# arduino_isp_v2.net
KiCad netlist of a schematic drawn in EAGLE
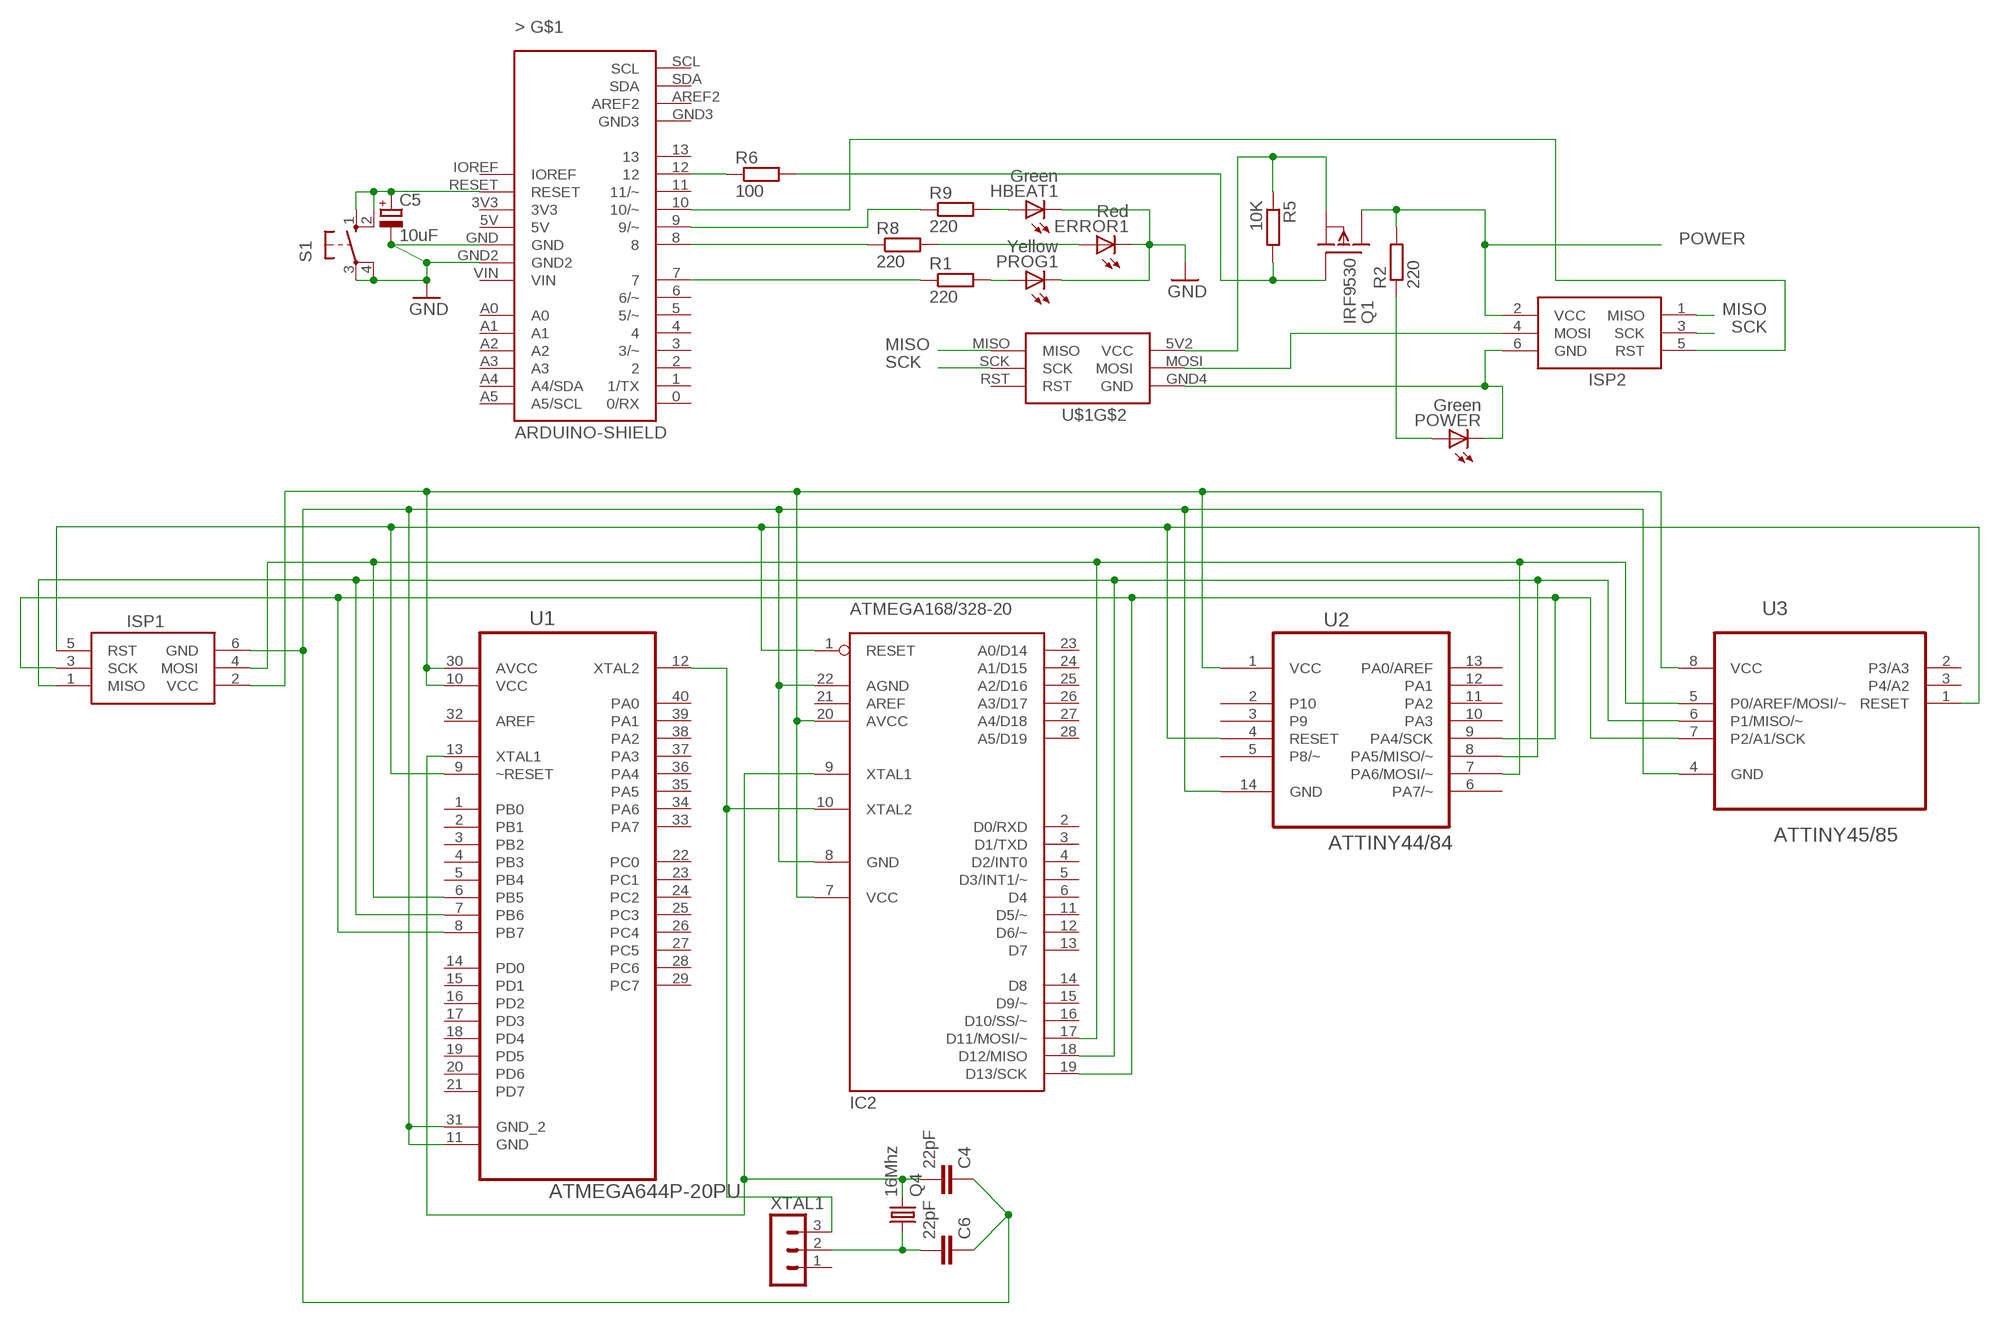
[diagram p0: schematic, sheet 1]

(export (version "E")
  (design (tool "Eeschema 10.0.6"))
  (components
    (comp (ref "C4")
      (value "22pF")
      (footprint "eagle-import:C050-030X075")
      (libsource (lib "eagle-import") (part "C-EU050-030X075"))
    )
    (comp (ref "C5")
      (value "10uF")
      (footprint "eagle-import:E2,5-6E")
      (libsource (lib "eagle-import") (part "CPOL-EUE2,5-6E"))
    )
    (comp (ref "C6")
      (value "22pF")
      (footprint "eagle-import:C050-030X075")
      (libsource (lib "eagle-import") (part "C-EU050-030X075"))
    )
    (comp (ref "ERROR1")
      (value "Red")
      (footprint "eagle-import:LED5MM")
      (libsource (lib "eagle-import") (part "LED5MM"))
    )
    (comp (ref "HBEAT1")
      (value "Green")
      (footprint "eagle-import:LED5MM")
      (libsource (lib "eagle-import") (part "LED5MM"))
    )
    (comp (ref "IC2")
      (value "ATMEGA168/328-20")
      (footprint "eagle-import:DIL28-3")
      (libsource (lib "eagle-import") (part "ATMEGA168/328-20"))
    )
    (comp (ref "ISP1")
      (value "AVRISP-6")
      (footprint "eagle-import:AVRISP")
      (libsource (lib "eagle-import") (part "AVRISP-6"))
    )
    (comp (ref "ISP2")
      (value "AVRISP-6")
      (footprint "eagle-import:AVRISP")
      (libsource (lib "eagle-import") (part "AVRISP-6"))
    )
    (comp (ref "POWER")
      (value "Green")
      (footprint "eagle-import:LED5MM")
      (libsource (lib "eagle-import") (part "LED5MM"))
    )
    (comp (ref "PROG1")
      (value "Yellow")
      (footprint "eagle-import:LED5MM")
      (libsource (lib "eagle-import") (part "LED5MM"))
    )
    (comp (ref "Q1")
      (value "IRF9530")
      (footprint "eagle-import:TO220")
      (libsource (lib "eagle-import") (part "IRF9530"))
    )
    (comp (ref "Q4")
      (value "16Mhz")
      (footprint "eagle-import:HC49_S")
      (fields (field (name "OC_FARNELL") "1667008"))
      (libsource (lib "eagle-import") (part "CRYSTALHC49S"))
    )
    (comp (ref "R1")
      (value "220")
      (footprint "eagle-import:0207_10")
      (libsource (lib "eagle-import") (part "R-EU_0207/10"))
    )
    (comp (ref "R2")
      (value "220")
      (footprint "eagle-import:0207_10")
      (libsource (lib "eagle-import") (part "R-EU_0207/10"))
    )
    (comp (ref "R5")
      (value "10K")
      (footprint "eagle-import:0207_10")
      (libsource (lib "eagle-import") (part "R-EU_0207/10"))
    )
    (comp (ref "R6")
      (value "100")
      (footprint "eagle-import:0207_10")
      (libsource (lib "eagle-import") (part "R-EU_0207/10"))
    )
    (comp (ref "R8")
      (value "220")
      (footprint "eagle-import:0207_10")
      (libsource (lib "eagle-import") (part "R-EU_0207/10"))
    )
    (comp (ref "R9")
      (value "220")
      (footprint "eagle-import:0207_10")
      (libsource (lib "eagle-import") (part "R-EU_0207/10"))
    )
    (comp (ref "S1")
      (value "10-XX")
      (footprint "eagle-import:B3F-10XX")
      (fields (field (name "MPN") "B3F-1000"))
      (libsource (lib "eagle-import") (part "10-XX"))
    )
    (comp (ref "U$1")
      (value "ARDUINO-SHIELD")
      (footprint "eagle-import:ARDUINO-UNO-SHIELD")
      (libsource (lib "eagle-import") (part "ARDUINO-SHIELD"))
    )
    (comp (ref "U1")
      (value "ATMEGA644P-20PU")
      (footprint "eagle-import:DIP254P1524X482-40")
      (libsource (lib "eagle-import") (part "ATMEGA644P-20PU"))
    )
    (comp (ref "U2")
      (value "ATTINY44/84")
      (footprint "eagle-import:DIP254P762X533-14")
      (fields (field (name "MPN") "ATTINY44-20PU"))
      (libsource (lib "eagle-import") (part "ATTINY44/84"))
    )
    (comp (ref "U3")
      (value "ATTINY45/85")
      (footprint "eagle-import:DIP254P762X533-8")
      (fields (field (name "MPN") "ATTINY45-20PU"))
      (libsource (lib "eagle-import") (part "ATTINY45/85"))
    )
    (comp (ref "XTAL1")
      (value "MA03-1")
      (footprint "eagle-import:MA03-1")
      (fields (field (name "OC_FARNELL") "unknown") (field (name "OC_NEWARK") "unknown"))
      (libsource (lib "eagle-import") (part "MA03-1"))
    )
  )
  (nets
    (net (code "1") (name "/MISO") (class "Default")
      (node (ref "ISP2") (pin "1") (pinfunction "MISO_1") (pintype "input"))
      (node (ref "U$1") (pin "MISO") (pinfunction "MISO_MISO") (pintype "input"))
    )
    (net (code "2") (name "/POWER") (class "Default")
      (node (ref "ISP2") (pin "2") (pinfunction "VCC_2") (pintype "power_in"))
      (node (ref "Q1") (pin "2") (pinfunction "D_2") (pintype "passive"))
      (node (ref "R2") (pin "2") (pinfunction "2_2") (pintype "passive"))
    )
    (net (code "3") (name "/SCK") (class "Default")
      (node (ref "ISP2") (pin "3") (pinfunction "SCK_3") (pintype "output"))
      (node (ref "U$1") (pin "SCK") (pinfunction "SCK_SCK") (pintype "output"))
    )
    (net (code "4") (name "GND") (class "Default")
      (node (ref "C5") (pin "-") (pinfunction "-_-") (pintype "passive"))
      (node (ref "ERROR1") (pin "K") (pinfunction "C_K") (pintype "passive"))
      (node (ref "HBEAT1") (pin "K") (pinfunction "C_K") (pintype "passive"))
      (node (ref "PROG1") (pin "K") (pinfunction "C_K") (pintype "passive"))
      (node (ref "S1") (pin "3") (pinfunction "P_3") (pintype "passive"))
      (node (ref "S1") (pin "4") (pinfunction "P1_4") (pintype "passive"))
      (node (ref "U$1") (pin "GND") (pinfunction "GND_GND") (pintype "bidirectional"))
      (node (ref "U$1") (pin "GND2") (pinfunction "GND2_GND2") (pintype "bidirectional"))
    )
    (net (code "5") (name "Net-(C6-Pad2)") (class "Default")
      (node (ref "C6") (pin "2") (pinfunction "2_2") (pintype "passive"))
      (node (ref "Q4") (pin "1") (pinfunction "1_1") (pintype "passive"))
      (node (ref "XTAL1") (pin "2") (pinfunction "2_2") (pintype "passive"))
    )
    (net (code "6") (name "Net-(ERROR1-PadA)") (class "Default")
      (node (ref "ERROR1") (pin "A") (pinfunction "A_A") (pintype "passive"))
      (node (ref "R8") (pin "2") (pinfunction "2_2") (pintype "passive"))
    )
    (net (code "7") (name "Net-(HBEAT1-PadA)") (class "Default")
      (node (ref "HBEAT1") (pin "A") (pinfunction "A_A") (pintype "passive"))
      (node (ref "R9") (pin "2") (pinfunction "2_2") (pintype "passive"))
    )
    (net (code "8") (name "Net-(IC2-AGND)") (class "Default")
      (node (ref "C4") (pin "1") (pinfunction "1_1") (pintype "passive"))
      (node (ref "C6") (pin "1") (pinfunction "1_1") (pintype "passive"))
      (node (ref "IC2") (pin "22") (pinfunction "AGND_22") (pintype "bidirectional"))
      (node (ref "IC2") (pin "8") (pinfunction "GND_8") (pintype "bidirectional"))
      (node (ref "ISP1") (pin "6") (pinfunction "GND_6") (pintype "power_in"))
      (node (ref "U1") (pin "11") (pinfunction "GND_11") (pintype "passive"))
      (node (ref "U1") (pin "31") (pinfunction "GND_2_31") (pintype "passive"))
      (node (ref "U2") (pin "14") (pinfunction "GND_14") (pintype "passive"))
      (node (ref "U3") (pin "4") (pinfunction "GND_4") (pintype "passive"))
    )
    (net (code "9") (name "Net-(IC2-AVCC)") (class "Default")
      (node (ref "IC2") (pin "20") (pinfunction "AVCC_20") (pintype "bidirectional"))
      (node (ref "IC2") (pin "7") (pinfunction "VCC_7") (pintype "bidirectional"))
      (node (ref "ISP1") (pin "2") (pinfunction "VCC_2") (pintype "power_in"))
      (node (ref "U1") (pin "10") (pinfunction "VCC_10") (pintype "power_in"))
      (node (ref "U1") (pin "30") (pinfunction "AVCC_30") (pintype "power_in"))
      (node (ref "U2") (pin "1") (pinfunction "VCC_1") (pintype "power_in"))
      (node (ref "U3") (pin "8") (pinfunction "VCC_8") (pintype "power_in"))
    )
    (net (code "10") (name "Net-(IC2-D11{slash}MOSI{slash}~{})") (class "Default")
      (node (ref "IC2") (pin "17") (pinfunction "D11/MOSI/~{}_17") (pintype "bidirectional"))
      (node (ref "ISP1") (pin "4") (pinfunction "MOSI_4") (pintype "output"))
      (node (ref "U1") (pin "6") (pinfunction "PB5_6") (pintype "bidirectional"))
      (node (ref "U2") (pin "7") (pinfunction "PA6/MOSI/~{}_7") (pintype "bidirectional"))
      (node (ref "U3") (pin "5") (pinfunction "P0/AREF/MOSI/~{}_5") (pintype "bidirectional"))
    )
    (net (code "11") (name "Net-(IC2-D12{slash}MISO)") (class "Default")
      (node (ref "IC2") (pin "18") (pinfunction "D12/MISO_18") (pintype "bidirectional"))
      (node (ref "ISP1") (pin "1") (pinfunction "MISO_1") (pintype "input"))
      (node (ref "U1") (pin "7") (pinfunction "PB6_7") (pintype "bidirectional"))
      (node (ref "U2") (pin "8") (pinfunction "PA5/MISO/~{}_8") (pintype "bidirectional"))
      (node (ref "U3") (pin "6") (pinfunction "P1/MISO/~{}_6") (pintype "bidirectional"))
    )
    (net (code "12") (name "Net-(IC2-D13{slash}SCK)") (class "Default")
      (node (ref "IC2") (pin "19") (pinfunction "D13/SCK_19") (pintype "bidirectional"))
      (node (ref "ISP1") (pin "3") (pinfunction "SCK_3") (pintype "output"))
      (node (ref "U1") (pin "8") (pinfunction "PB7_8") (pintype "bidirectional"))
      (node (ref "U2") (pin "9") (pinfunction "PA4/SCK_9") (pintype "bidirectional"))
      (node (ref "U3") (pin "7") (pinfunction "P2/A1/SCK_7") (pintype "bidirectional"))
    )
    (net (code "13") (name "Net-(IC2-RESET)") (class "Default")
      (node (ref "IC2") (pin "1") (pinfunction "RESET_1") (pintype "bidirectional"))
      (node (ref "ISP1") (pin "5") (pinfunction "RST_5") (pintype "output"))
      (node (ref "U1") (pin "9") (pinfunction "~{RESET}_9") (pintype "input"))
      (node (ref "U2") (pin "4") (pinfunction "RESET_4") (pintype "bidirectional"))
      (node (ref "U3") (pin "1") (pinfunction "RESET_1") (pintype "bidirectional"))
    )
    (net (code "14") (name "Net-(IC2-XTAL1)") (class "Default")
      (node (ref "C4") (pin "2") (pinfunction "2_2") (pintype "passive"))
      (node (ref "IC2") (pin "9") (pinfunction "XTAL1_9") (pintype "bidirectional"))
      (node (ref "Q4") (pin "2") (pinfunction "2_2") (pintype "passive"))
      (node (ref "U1") (pin "13") (pinfunction "XTAL1_13") (pintype "input"))
    )
    (net (code "15") (name "Net-(IC2-XTAL2)") (class "Default")
      (node (ref "IC2") (pin "10") (pinfunction "XTAL2_10") (pintype "bidirectional"))
      (node (ref "U1") (pin "12") (pinfunction "XTAL2_12") (pintype "output"))
      (node (ref "XTAL1") (pin "3") (pinfunction "3_3") (pintype "passive"))
    )
    (net (code "16") (name "Net-(ISP2-GND)") (class "Default")
      (node (ref "ISP2") (pin "6") (pinfunction "GND_6") (pintype "power_in"))
      (node (ref "POWER") (pin "K") (pinfunction "C_K") (pintype "passive"))
      (node (ref "U$1") (pin "GND4") (pinfunction "GND_GND4") (pintype "power_in"))
    )
    (net (code "17") (name "Net-(ISP2-MOSI)") (class "Default")
      (node (ref "ISP2") (pin "4") (pinfunction "MOSI_4") (pintype "output"))
      (node (ref "U$1") (pin "MOSI") (pinfunction "MOSI_MOSI") (pintype "output"))
    )
    (net (code "18") (name "Net-(ISP2-RST)") (class "Default")
      (node (ref "ISP2") (pin "5") (pinfunction "RST_5") (pintype "output"))
      (node (ref "U$1") (pin "10") (pinfunction "10/~{}_10") (pintype "bidirectional"))
    )
    (net (code "19") (name "Net-(POWER-PadA)") (class "Default")
      (node (ref "POWER") (pin "A") (pinfunction "A_A") (pintype "passive"))
      (node (ref "R2") (pin "1") (pinfunction "1_1") (pintype "passive"))
    )
    (net (code "20") (name "Net-(PROG1-PadA)") (class "Default")
      (node (ref "PROG1") (pin "A") (pinfunction "A_A") (pintype "passive"))
      (node (ref "R1") (pin "2") (pinfunction "2_2") (pintype "passive"))
    )
    (net (code "21") (name "Net-(Q1-G)") (class "Default")
      (node (ref "Q1") (pin "1") (pinfunction "G_1") (pintype "passive"))
      (node (ref "R5") (pin "2") (pinfunction "2_2") (pintype "passive"))
      (node (ref "R6") (pin "2") (pinfunction "2_2") (pintype "passive"))
    )
    (net (code "22") (name "Net-(Q1-S)") (class "Default")
      (node (ref "Q1") (pin "3") (pinfunction "S_3") (pintype "passive"))
      (node (ref "R5") (pin "1") (pinfunction "1_1") (pintype "passive"))
      (node (ref "U$1") (pin "5V2") (pinfunction "VCC_5V2") (pintype "power_in"))
    )
    (net (code "23") (name "Net-(R1-Pad1)") (class "Default")
      (node (ref "R1") (pin "1") (pinfunction "1_1") (pintype "passive"))
      (node (ref "U$1") (pin "7") (pinfunction "7_7") (pintype "bidirectional"))
    )
    (net (code "24") (name "Net-(R6-Pad1)") (class "Default")
      (node (ref "R6") (pin "1") (pinfunction "1_1") (pintype "passive"))
      (node (ref "U$1") (pin "12") (pinfunction "12_12") (pintype "bidirectional"))
    )
    (net (code "25") (name "Net-(R8-Pad1)") (class "Default")
      (node (ref "R8") (pin "1") (pinfunction "1_1") (pintype "passive"))
      (node (ref "U$1") (pin "8") (pinfunction "8_8") (pintype "bidirectional"))
    )
    (net (code "26") (name "Net-(S1-S)") (class "Default")
      (node (ref "C5") (pin "+") (pinfunction "+_+") (pintype "passive"))
      (node (ref "S1") (pin "1") (pinfunction "S_1") (pintype "passive"))
      (node (ref "S1") (pin "2") (pinfunction "S1_2") (pintype "passive"))
      (node (ref "U$1") (pin "RESET") (pinfunction "RESET_RESET") (pintype "bidirectional"))
    )
    (net (code "27") (name "Net-(U$1A-9{slash}~{})") (class "Default")
      (node (ref "R9") (pin "1") (pinfunction "1_1") (pintype "passive"))
      (node (ref "U$1") (pin "9") (pinfunction "9/~{}_9") (pintype "bidirectional"))
    )
    (net (code "28") (name "unconnected-(IC2-A0{slash}D14-Pad23)") (class "Default")
      (node (ref "IC2") (pin "23") (pinfunction "A0/D14_23") (pintype "bidirectional"))
    )
    (net (code "29") (name "unconnected-(IC2-A1{slash}D15-Pad24)") (class "Default")
      (node (ref "IC2") (pin "24") (pinfunction "A1/D15_24") (pintype "bidirectional"))
    )
    (net (code "30") (name "unconnected-(IC2-A2{slash}D16-Pad25)") (class "Default")
      (node (ref "IC2") (pin "25") (pinfunction "A2/D16_25") (pintype "bidirectional"))
    )
    (net (code "31") (name "unconnected-(IC2-A3{slash}D17-Pad26)") (class "Default")
      (node (ref "IC2") (pin "26") (pinfunction "A3/D17_26") (pintype "bidirectional"))
    )
    (net (code "32") (name "unconnected-(IC2-A4{slash}D18-Pad27)") (class "Default")
      (node (ref "IC2") (pin "27") (pinfunction "A4/D18_27") (pintype "bidirectional"))
    )
    (net (code "33") (name "unconnected-(IC2-A5{slash}D19-Pad28)") (class "Default")
      (node (ref "IC2") (pin "28") (pinfunction "A5/D19_28") (pintype "bidirectional"))
    )
    (net (code "34") (name "unconnected-(IC2-AREF-Pad21)") (class "Default")
      (node (ref "IC2") (pin "21") (pinfunction "AREF_21") (pintype "bidirectional"))
    )
    (net (code "35") (name "unconnected-(IC2-D0{slash}RXD-Pad2)") (class "Default")
      (node (ref "IC2") (pin "2") (pinfunction "D0/RXD_2") (pintype "bidirectional"))
    )
    (net (code "36") (name "unconnected-(IC2-D1{slash}TXD-Pad3)") (class "Default")
      (node (ref "IC2") (pin "3") (pinfunction "D1/TXD_3") (pintype "bidirectional"))
    )
    (net (code "37") (name "unconnected-(IC2-D2{slash}INT0-Pad4)") (class "Default")
      (node (ref "IC2") (pin "4") (pinfunction "D2/INT0_4") (pintype "bidirectional"))
    )
    (net (code "38") (name "unconnected-(IC2-D3{slash}INT1{slash}~{}-Pad5)") (class "Default")
      (node (ref "IC2") (pin "5") (pinfunction "D3/INT1/~{}_5") (pintype "bidirectional"))
    )
    (net (code "39") (name "unconnected-(IC2-D4-Pad6)") (class "Default")
      (node (ref "IC2") (pin "6") (pinfunction "D4_6") (pintype "bidirectional"))
    )
    (net (code "40") (name "unconnected-(IC2-D5{slash}~{}-Pad11)") (class "Default")
      (node (ref "IC2") (pin "11") (pinfunction "D5/~{}_11") (pintype "bidirectional"))
    )
    (net (code "41") (name "unconnected-(IC2-D6{slash}~{}-Pad12)") (class "Default")
      (node (ref "IC2") (pin "12") (pinfunction "D6/~{}_12") (pintype "bidirectional"))
    )
    (net (code "42") (name "unconnected-(IC2-D7-Pad13)") (class "Default")
      (node (ref "IC2") (pin "13") (pinfunction "D7_13") (pintype "bidirectional"))
    )
    (net (code "43") (name "unconnected-(IC2-D8-Pad14)") (class "Default")
      (node (ref "IC2") (pin "14") (pinfunction "D8_14") (pintype "bidirectional"))
    )
    (net (code "44") (name "unconnected-(IC2-D9{slash}~{}-Pad15)") (class "Default")
      (node (ref "IC2") (pin "15") (pinfunction "D9/~{}_15") (pintype "bidirectional"))
    )
    (net (code "45") (name "unconnected-(IC2-D10{slash}SS{slash}~{}-Pad16)") (class "Default")
      (node (ref "IC2") (pin "16") (pinfunction "D10/SS/~{}_16") (pintype "bidirectional"))
    )
    (net (code "46") (name "unconnected-(U$1-Pad2)") (class "Default")
      (node (ref "U$1") (pin "2") (pinfunction "2_2") (pintype "bidirectional"))
    )
    (net (code "47") (name "unconnected-(U$1-Pad3V3)") (class "Default")
      (node (ref "U$1") (pin "3V3") (pinfunction "3V3_3V3") (pintype "bidirectional"))
    )
    (net (code "48") (name "unconnected-(U$1-Pad4)") (class "Default")
      (node (ref "U$1") (pin "4") (pinfunction "4_4") (pintype "bidirectional"))
    )
    (net (code "49") (name "unconnected-(U$1-Pad5V)") (class "Default")
      (node (ref "U$1") (pin "5V") (pinfunction "5V_5V") (pintype "bidirectional"))
    )
    (net (code "50") (name "unconnected-(U$1-Pad13)") (class "Default")
      (node (ref "U$1") (pin "13") (pinfunction "13_13") (pintype "bidirectional"))
    )
    (net (code "51") (name "unconnected-(U$1-PadA0)") (class "Default")
      (node (ref "U$1") (pin "A0") (pinfunction "A0_A0") (pintype "bidirectional"))
    )
    (net (code "52") (name "unconnected-(U$1-PadA1)") (class "Default")
      (node (ref "U$1") (pin "A1") (pinfunction "A1_A1") (pintype "bidirectional"))
    )
    (net (code "53") (name "unconnected-(U$1-PadA2)") (class "Default")
      (node (ref "U$1") (pin "A2") (pinfunction "A2_A2") (pintype "bidirectional"))
    )
    (net (code "54") (name "unconnected-(U$1-PadA3)") (class "Default")
      (node (ref "U$1") (pin "A3") (pinfunction "A3_A3") (pintype "bidirectional"))
    )
    (net (code "55") (name "unconnected-(U$1-PadAREF2)") (class "Default")
      (node (ref "U$1") (pin "AREF2") (pinfunction "AREF2_AREF2") (pintype "bidirectional"))
    )
    (net (code "56") (name "unconnected-(U$1-PadGND3)") (class "Default")
      (node (ref "U$1") (pin "GND3") (pinfunction "GND3_GND3") (pintype "bidirectional"))
    )
    (net (code "57") (name "unconnected-(U$1-PadIOREF)") (class "Default")
      (node (ref "U$1") (pin "IOREF") (pinfunction "IOREF_IOREF") (pintype "bidirectional"))
    )
    (net (code "58") (name "unconnected-(U$1-PadRST)") (class "Default")
      (node (ref "U$1") (pin "RST") (pinfunction "RST_RST") (pintype "output"))
    )
    (net (code "59") (name "unconnected-(U$1-PadSCL)") (class "Default")
      (node (ref "U$1") (pin "SCL") (pinfunction "SCL_SCL") (pintype "bidirectional"))
    )
    (net (code "60") (name "unconnected-(U$1-PadSDA)") (class "Default")
      (node (ref "U$1") (pin "SDA") (pinfunction "SDA_SDA") (pintype "bidirectional"))
    )
    (net (code "61") (name "unconnected-(U$1-PadVIN)") (class "Default")
      (node (ref "U$1") (pin "VIN") (pinfunction "VIN_VIN") (pintype "bidirectional"))
    )
    (net (code "62") (name "unconnected-(U$1A-0{slash}RX-Pad0)") (class "Default")
      (node (ref "U$1") (pin "0") (pinfunction "0/RX_0") (pintype "bidirectional"))
    )
    (net (code "63") (name "unconnected-(U$1A-1{slash}TX-Pad1)") (class "Default")
      (node (ref "U$1") (pin "1") (pinfunction "1/TX_1") (pintype "bidirectional"))
    )
    (net (code "64") (name "unconnected-(U$1A-3{slash}~{}-Pad3)") (class "Default")
      (node (ref "U$1") (pin "3") (pinfunction "3/~{}_3") (pintype "bidirectional"))
    )
    (net (code "65") (name "unconnected-(U$1A-5{slash}~{}-Pad5)") (class "Default")
      (node (ref "U$1") (pin "5") (pinfunction "5/~{}_5") (pintype "bidirectional"))
    )
    (net (code "66") (name "unconnected-(U$1A-6{slash}~{}-Pad6)") (class "Default")
      (node (ref "U$1") (pin "6") (pinfunction "6/~{}_6") (pintype "bidirectional"))
    )
    (net (code "67") (name "unconnected-(U$1A-11{slash}~{}-Pad11)") (class "Default")
      (node (ref "U$1") (pin "11") (pinfunction "11/~{}_11") (pintype "bidirectional"))
    )
    (net (code "68") (name "unconnected-(U$1A-A4{slash}SDA-PadA4)") (class "Default")
      (node (ref "U$1") (pin "A4") (pinfunction "A4/SDA_A4") (pintype "bidirectional"))
    )
    (net (code "69") (name "unconnected-(U$1A-A5{slash}SCL-PadA5)") (class "Default")
      (node (ref "U$1") (pin "A5") (pinfunction "A5/SCL_A5") (pintype "bidirectional"))
    )
    (net (code "70") (name "unconnected-(U1-AREF-Pad32)") (class "Default")
      (node (ref "U1") (pin "32") (pinfunction "AREF_32") (pintype "input"))
    )
    (net (code "71") (name "unconnected-(U1-PA0-Pad40)") (class "Default")
      (node (ref "U1") (pin "40") (pinfunction "PA0_40") (pintype "bidirectional"))
    )
    (net (code "72") (name "unconnected-(U1-PA1-Pad39)") (class "Default")
      (node (ref "U1") (pin "39") (pinfunction "PA1_39") (pintype "bidirectional"))
    )
    (net (code "73") (name "unconnected-(U1-PA2-Pad38)") (class "Default")
      (node (ref "U1") (pin "38") (pinfunction "PA2_38") (pintype "bidirectional"))
    )
    (net (code "74") (name "unconnected-(U1-PA3-Pad37)") (class "Default")
      (node (ref "U1") (pin "37") (pinfunction "PA3_37") (pintype "bidirectional"))
    )
    (net (code "75") (name "unconnected-(U1-PA4-Pad36)") (class "Default")
      (node (ref "U1") (pin "36") (pinfunction "PA4_36") (pintype "bidirectional"))
    )
    (net (code "76") (name "unconnected-(U1-PA5-Pad35)") (class "Default")
      (node (ref "U1") (pin "35") (pinfunction "PA5_35") (pintype "bidirectional"))
    )
    (net (code "77") (name "unconnected-(U1-PA6-Pad34)") (class "Default")
      (node (ref "U1") (pin "34") (pinfunction "PA6_34") (pintype "bidirectional"))
    )
    (net (code "78") (name "unconnected-(U1-PA7-Pad33)") (class "Default")
      (node (ref "U1") (pin "33") (pinfunction "PA7_33") (pintype "bidirectional"))
    )
    (net (code "79") (name "unconnected-(U1-PB0-Pad1)") (class "Default")
      (node (ref "U1") (pin "1") (pinfunction "PB0_1") (pintype "bidirectional"))
    )
    (net (code "80") (name "unconnected-(U1-PB1-Pad2)") (class "Default")
      (node (ref "U1") (pin "2") (pinfunction "PB1_2") (pintype "bidirectional"))
    )
    (net (code "81") (name "unconnected-(U1-PB2-Pad3)") (class "Default")
      (node (ref "U1") (pin "3") (pinfunction "PB2_3") (pintype "bidirectional"))
    )
    (net (code "82") (name "unconnected-(U1-PB3-Pad4)") (class "Default")
      (node (ref "U1") (pin "4") (pinfunction "PB3_4") (pintype "bidirectional"))
    )
    (net (code "83") (name "unconnected-(U1-PB4-Pad5)") (class "Default")
      (node (ref "U1") (pin "5") (pinfunction "PB4_5") (pintype "bidirectional"))
    )
    (net (code "84") (name "unconnected-(U1-PC0-Pad22)") (class "Default")
      (node (ref "U1") (pin "22") (pinfunction "PC0_22") (pintype "bidirectional"))
    )
    (net (code "85") (name "unconnected-(U1-PC1-Pad23)") (class "Default")
      (node (ref "U1") (pin "23") (pinfunction "PC1_23") (pintype "bidirectional"))
    )
    (net (code "86") (name "unconnected-(U1-PC2-Pad24)") (class "Default")
      (node (ref "U1") (pin "24") (pinfunction "PC2_24") (pintype "bidirectional"))
    )
    (net (code "87") (name "unconnected-(U1-PC3-Pad25)") (class "Default")
      (node (ref "U1") (pin "25") (pinfunction "PC3_25") (pintype "bidirectional"))
    )
    (net (code "88") (name "unconnected-(U1-PC4-Pad26)") (class "Default")
      (node (ref "U1") (pin "26") (pinfunction "PC4_26") (pintype "bidirectional"))
    )
    (net (code "89") (name "unconnected-(U1-PC5-Pad27)") (class "Default")
      (node (ref "U1") (pin "27") (pinfunction "PC5_27") (pintype "bidirectional"))
    )
    (net (code "90") (name "unconnected-(U1-PC6-Pad28)") (class "Default")
      (node (ref "U1") (pin "28") (pinfunction "PC6_28") (pintype "bidirectional"))
    )
    (net (code "91") (name "unconnected-(U1-PC7-Pad29)") (class "Default")
      (node (ref "U1") (pin "29") (pinfunction "PC7_29") (pintype "bidirectional"))
    )
    (net (code "92") (name "unconnected-(U1-PD0-Pad14)") (class "Default")
      (node (ref "U1") (pin "14") (pinfunction "PD0_14") (pintype "bidirectional"))
    )
    (net (code "93") (name "unconnected-(U1-PD1-Pad15)") (class "Default")
      (node (ref "U1") (pin "15") (pinfunction "PD1_15") (pintype "bidirectional"))
    )
    (net (code "94") (name "unconnected-(U1-PD2-Pad16)") (class "Default")
      (node (ref "U1") (pin "16") (pinfunction "PD2_16") (pintype "bidirectional"))
    )
    (net (code "95") (name "unconnected-(U1-PD3-Pad17)") (class "Default")
      (node (ref "U1") (pin "17") (pinfunction "PD3_17") (pintype "bidirectional"))
    )
    (net (code "96") (name "unconnected-(U1-PD4-Pad18)") (class "Default")
      (node (ref "U1") (pin "18") (pinfunction "PD4_18") (pintype "bidirectional"))
    )
    (net (code "97") (name "unconnected-(U1-PD5-Pad19)") (class "Default")
      (node (ref "U1") (pin "19") (pinfunction "PD5_19") (pintype "bidirectional"))
    )
    (net (code "98") (name "unconnected-(U1-PD6-Pad20)") (class "Default")
      (node (ref "U1") (pin "20") (pinfunction "PD6_20") (pintype "bidirectional"))
    )
    (net (code "99") (name "unconnected-(U1-PD7-Pad21)") (class "Default")
      (node (ref "U1") (pin "21") (pinfunction "PD7_21") (pintype "bidirectional"))
    )
    (net (code "100") (name "unconnected-(U2-P8{slash}~{}-Pad5)") (class "Default")
      (node (ref "U2") (pin "5") (pinfunction "P8/~{}_5") (pintype "bidirectional"))
    )
    (net (code "101") (name "unconnected-(U2-P9-Pad3)") (class "Default")
      (node (ref "U2") (pin "3") (pinfunction "P9_3") (pintype "bidirectional"))
    )
    (net (code "102") (name "unconnected-(U2-P10-Pad2)") (class "Default")
      (node (ref "U2") (pin "2") (pinfunction "P10_2") (pintype "bidirectional"))
    )
    (net (code "103") (name "unconnected-(U2-PA0{slash}AREF-Pad13)") (class "Default")
      (node (ref "U2") (pin "13") (pinfunction "PA0/AREF_13") (pintype "bidirectional"))
    )
    (net (code "104") (name "unconnected-(U2-PA1-Pad12)") (class "Default")
      (node (ref "U2") (pin "12") (pinfunction "PA1_12") (pintype "bidirectional"))
    )
    (net (code "105") (name "unconnected-(U2-PA2-Pad11)") (class "Default")
      (node (ref "U2") (pin "11") (pinfunction "PA2_11") (pintype "bidirectional"))
    )
    (net (code "106") (name "unconnected-(U2-PA3-Pad10)") (class "Default")
      (node (ref "U2") (pin "10") (pinfunction "PA3_10") (pintype "bidirectional"))
    )
    (net (code "107") (name "unconnected-(U2-PA7{slash}~{}-Pad6)") (class "Default")
      (node (ref "U2") (pin "6") (pinfunction "PA7/~{}_6") (pintype "bidirectional"))
    )
    (net (code "108") (name "unconnected-(U3-P3{slash}A3-Pad2)") (class "Default")
      (node (ref "U3") (pin "2") (pinfunction "P3/A3_2") (pintype "bidirectional"))
    )
    (net (code "109") (name "unconnected-(U3-P4{slash}A2-Pad3)") (class "Default")
      (node (ref "U3") (pin "3") (pinfunction "P4/A2_3") (pintype "bidirectional"))
    )
    (net (code "110") (name "unconnected-(XTAL1-Pad1)") (class "Default")
      (node (ref "XTAL1") (pin "1") (pinfunction "1_1") (pintype "passive"))
    )
  )
)
